# integrated_haptic.net
KiCad netlist of a schematic drawn in EAGLE
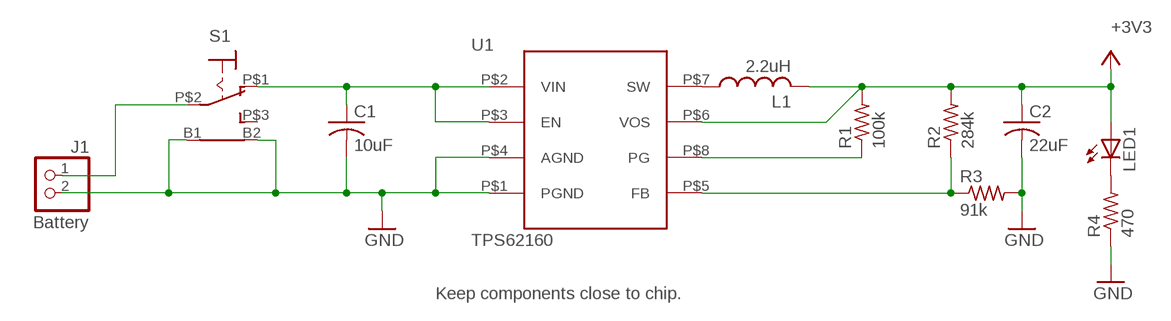
[diagram p0: schematic, sheet 1]
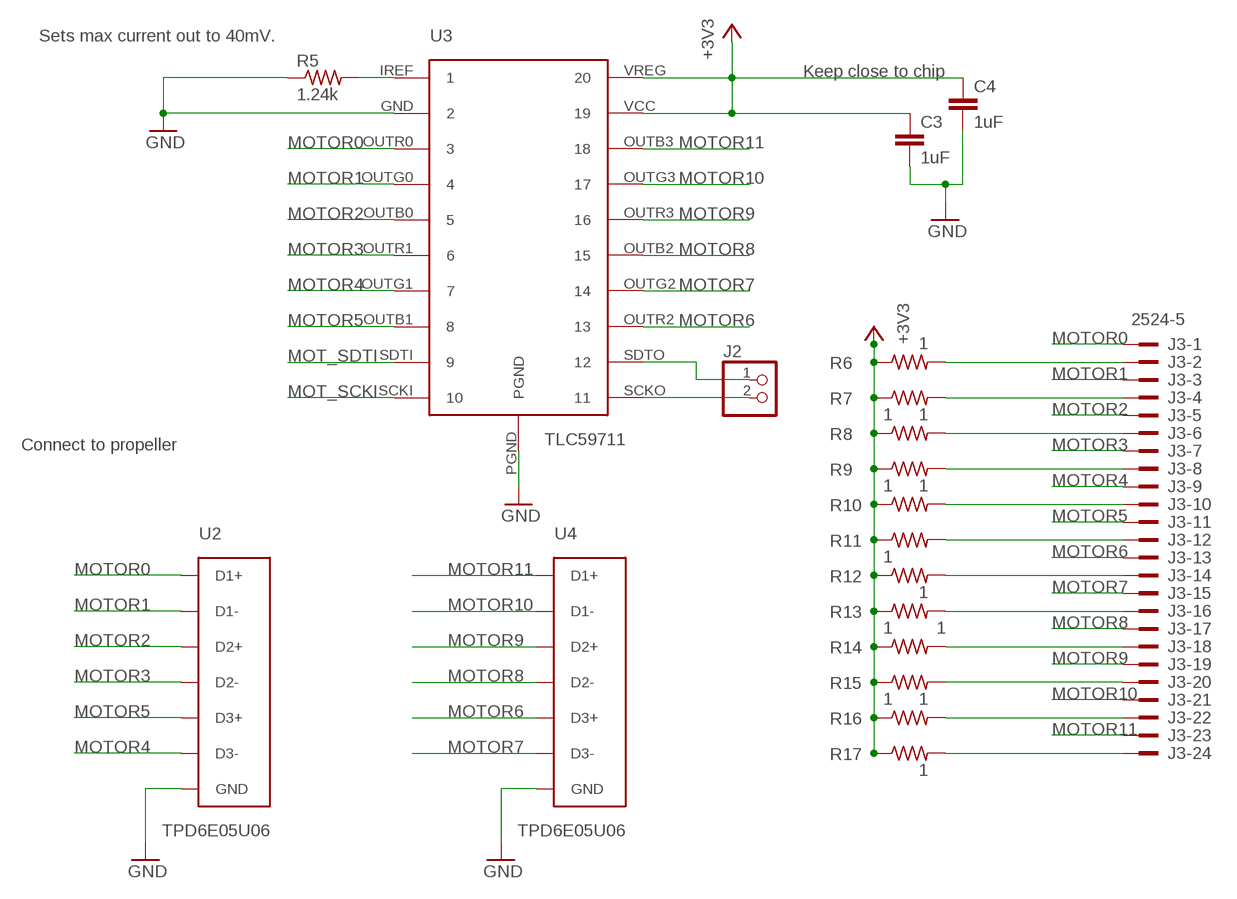
[diagram p1: schematic, sheet 2]
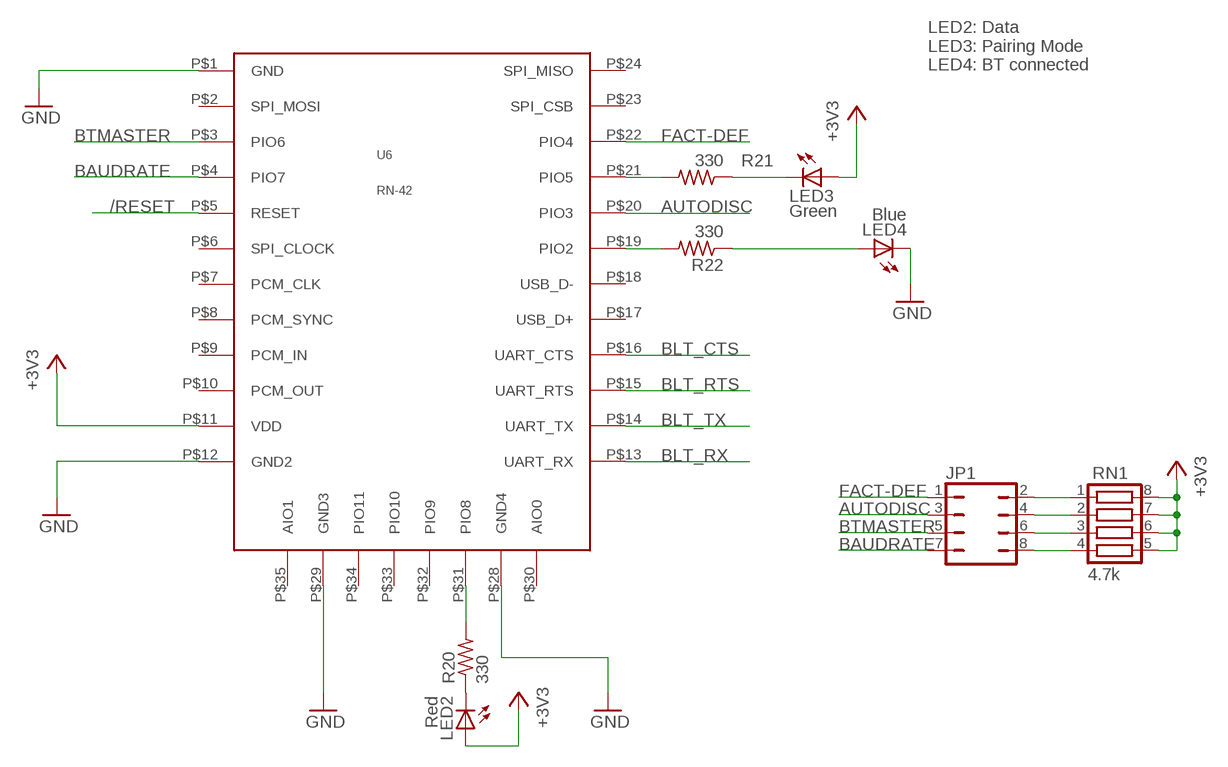
[diagram p2: schematic, sheet 3]
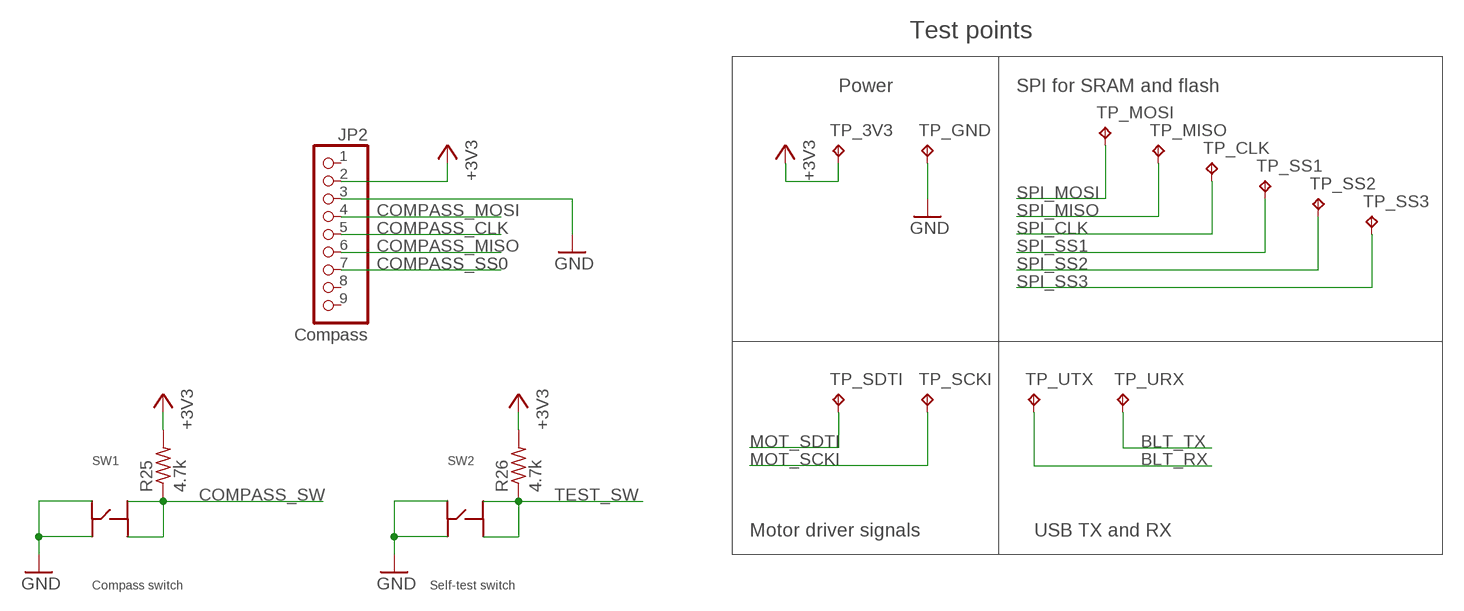
[diagram p3: schematic, sheet 4]
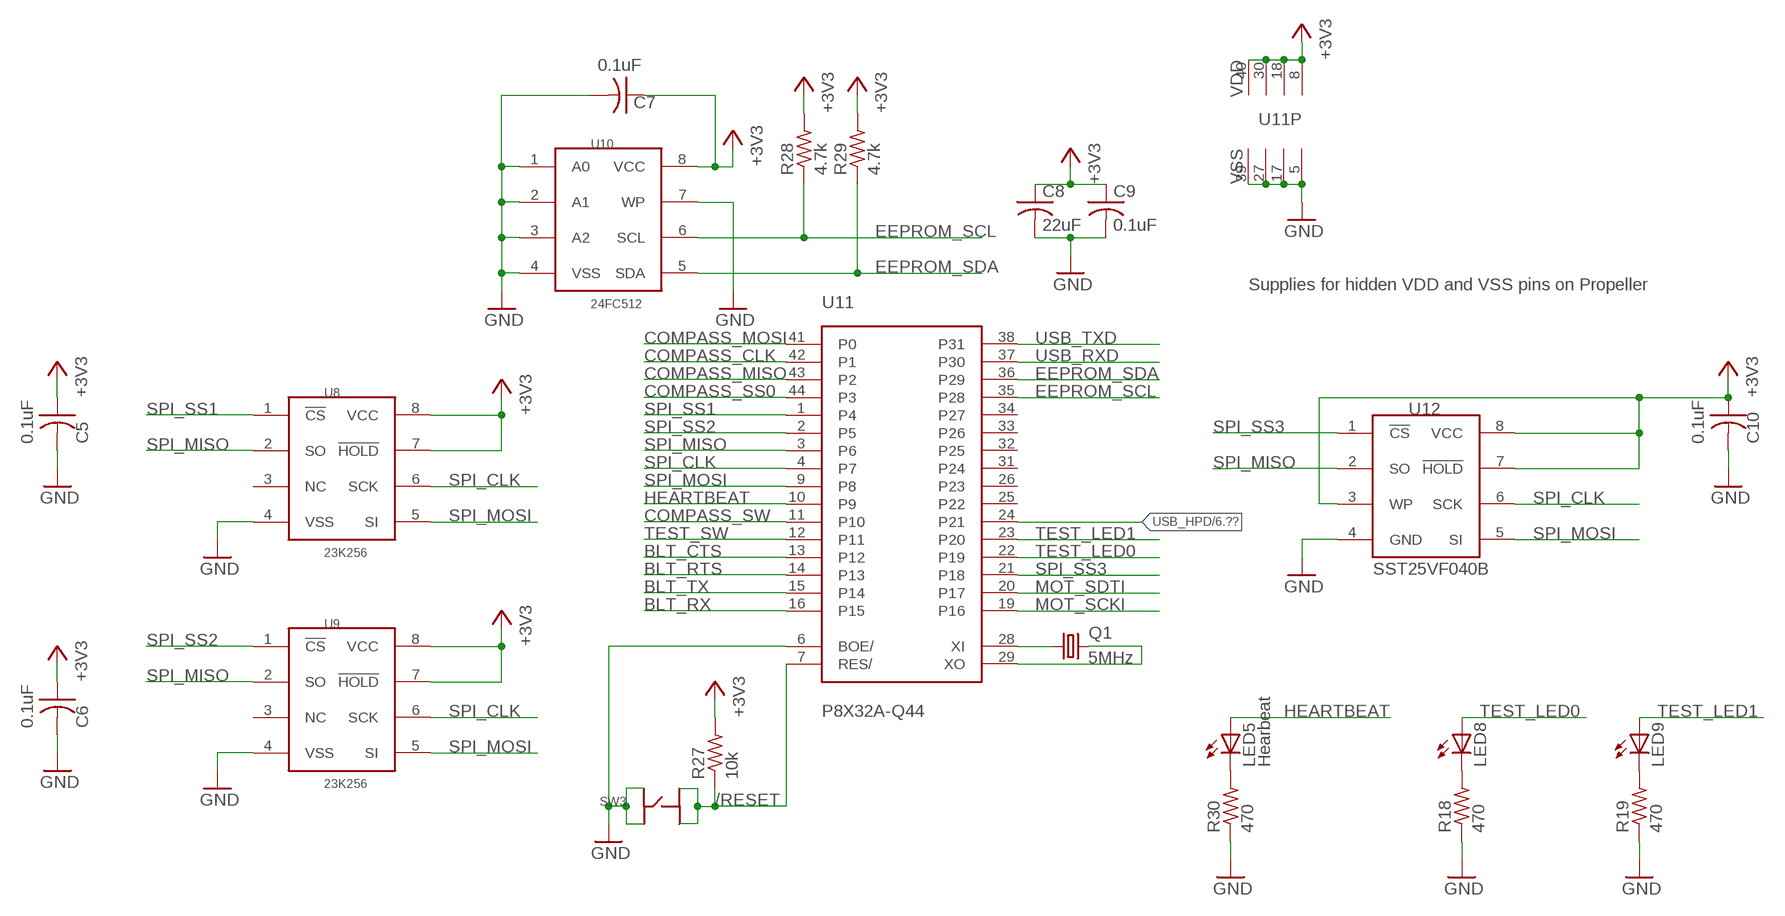
[diagram p4: schematic, sheet 5]
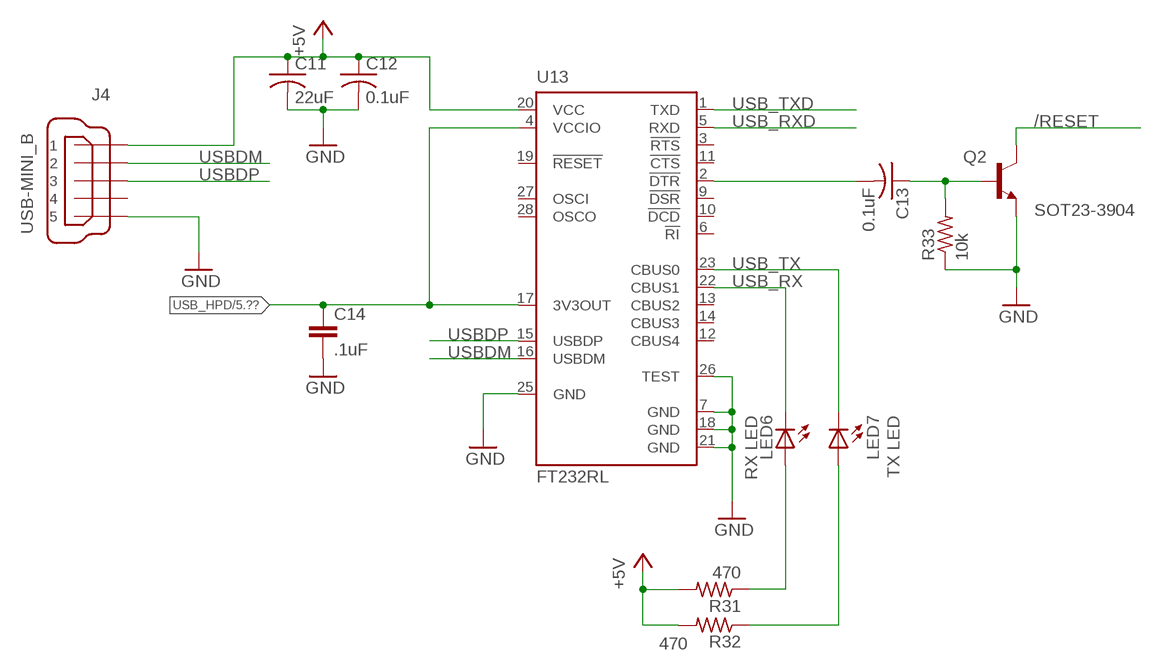
[diagram p5: schematic, sheet 6]

(export (version "E")
  (design (tool "Eeschema 10.0.6"))
  (components
    (comp (ref "C1")
      (value "10uF")
      (footprint "eagle-import:C1206K")
      (libsource (lib "eagle-import") (part "C-USC1206K"))
    )
    (comp (ref "C2")
      (value "22uF")
      (footprint "eagle-import:C1206K")
      (libsource (lib "eagle-import") (part "C-USC1206K"))
    )
    (comp (ref "J1")
      (value "Battery")
      (footprint "eagle-import:1X02")
      (libsource (lib "eagle-import") (part "PINHD-1X2"))
    )
    (comp (ref "L1")
      (value "2.2uH")
      (footprint "eagle-import:L2520P")
      (libsource (lib "eagle-import") (part "L-USL2520P"))
    )
    (comp (ref "LED1")
      (value "LEDCHIP-LED0805")
      (footprint "eagle-import:CHIP-LED0805")
      (libsource (lib "eagle-import") (part "LEDCHIP-LED0805"))
    )
    (comp (ref "R1")
      (value "100k")
      (footprint "eagle-import:R0603")
      (libsource (lib "eagle-import") (part "R-US_R0603"))
    )
    (comp (ref "R2")
      (value "284k")
      (footprint "eagle-import:R0603")
      (libsource (lib "eagle-import") (part "R-US_R0603"))
    )
    (comp (ref "R3")
      (value "91k")
      (footprint "eagle-import:R0603")
      (libsource (lib "eagle-import") (part "R-US_R0603"))
    )
    (comp (ref "R4")
      (value "470")
      (footprint "eagle-import:R0603")
      (libsource (lib "eagle-import") (part "R-US_R0603"))
    )
    (comp (ref "S1")
      (value "7101MD9AQE")
      (footprint "eagle-import:7101MD9A")
      (libsource (lib "eagle-import") (part "7101MD9AQE"))
    )
    (comp (ref "U1")
      (value "TPS62160")
      (footprint "eagle-import:VSSOP")
      (libsource (lib "eagle-import") (part "TPS62160"))
    )
    (comp (ref "JP2")
      (value "Compass")
      (footprint "eagle-import:1X09")
      (libsource (lib "eagle-import") (part "PINHD-1X9"))
    )
    (comp (ref "R25")
      (value "4.7k")
      (footprint "eagle-import:R0603")
      (libsource (lib "eagle-import") (part "R-US_R0603"))
    )
    (comp (ref "R26")
      (value "4.7k")
      (footprint "eagle-import:R0603")
      (libsource (lib "eagle-import") (part "R-US_R0603"))
    )
    (comp (ref "SW1")
      (value "Compass switch")
      (footprint "eagle-import:6MMX6MM")
      (libsource (lib "eagle-import") (part "PUSHBUTTON"))
    )
    (comp (ref "SW2")
      (value "Self-test switch")
      (footprint "eagle-import:6MMX6MM")
      (libsource (lib "eagle-import") (part "PUSHBUTTON"))
    )
    (comp (ref "TP_3V3")
      (value "TPPAD1-13")
      (footprint "eagle-import:P1-13")
      (libsource (lib "eagle-import") (part "TPPAD1-13"))
    )
    (comp (ref "TP_CLK")
      (value "TPPAD1-13")
      (footprint "eagle-import:P1-13")
      (libsource (lib "eagle-import") (part "TPPAD1-13"))
    )
    (comp (ref "TP_GND")
      (value "TPPAD1-13")
      (footprint "eagle-import:P1-13")
      (libsource (lib "eagle-import") (part "TPPAD1-13"))
    )
    (comp (ref "TP_MISO")
      (value "TPPAD1-13")
      (footprint "eagle-import:P1-13")
      (libsource (lib "eagle-import") (part "TPPAD1-13"))
    )
    (comp (ref "TP_MOSI")
      (value "SPI_MOSI")
      (footprint "eagle-import:P1-13")
      (libsource (lib "eagle-import") (part "TPPAD1-13"))
    )
    (comp (ref "TP_SCKI")
      (value "TPPAD1-13")
      (footprint "eagle-import:P1-13")
      (libsource (lib "eagle-import") (part "TPPAD1-13"))
    )
    (comp (ref "TP_SDTI")
      (value "TPPAD1-13")
      (footprint "eagle-import:P1-13")
      (libsource (lib "eagle-import") (part "TPPAD1-13"))
    )
    (comp (ref "TP_SS1")
      (value "TPPAD1-13")
      (footprint "eagle-import:P1-13")
      (libsource (lib "eagle-import") (part "TPPAD1-13"))
    )
    (comp (ref "TP_SS2")
      (value "TPPAD1-13")
      (footprint "eagle-import:P1-13")
      (libsource (lib "eagle-import") (part "TPPAD1-13"))
    )
    (comp (ref "TP_SS3")
      (value "TPPAD1-13")
      (footprint "eagle-import:P1-13")
      (libsource (lib "eagle-import") (part "TPPAD1-13"))
    )
    (comp (ref "TP_URX")
      (value "TPPAD1-13")
      (footprint "eagle-import:P1-13")
      (libsource (lib "eagle-import") (part "TPPAD1-13"))
    )
    (comp (ref "TP_UTX")
      (value "TPPAD1-13")
      (footprint "eagle-import:P1-13")
      (libsource (lib "eagle-import") (part "TPPAD1-13"))
    )
    (comp (ref "JP1")
      (value "JP4Q")
      (footprint "eagle-import:JP4Q")
      (libsource (lib "eagle-import") (part "JP4Q"))
    )
    (comp (ref "LED2")
      (value "Red")
      (footprint "eagle-import:CHIP-LED0805")
      (libsource (lib "eagle-import") (part "LEDCHIP-LED0805"))
    )
    (comp (ref "LED3")
      (value "Green")
      (footprint "eagle-import:CHIP-LED0805")
      (libsource (lib "eagle-import") (part "LEDCHIP-LED0805"))
    )
    (comp (ref "LED4")
      (value "Blue")
      (footprint "eagle-import:CHIP-LED0805")
      (libsource (lib "eagle-import") (part "LEDCHIP-LED0805"))
    )
    (comp (ref "R20")
      (value "330")
      (footprint "eagle-import:R0603")
      (libsource (lib "eagle-import") (part "R-US_R0603"))
    )
    (comp (ref "R21")
      (value "330")
      (footprint "eagle-import:R0603")
      (libsource (lib "eagle-import") (part "R-US_R0603"))
    )
    (comp (ref "R22")
      (value "330")
      (footprint "eagle-import:R0603")
      (libsource (lib "eagle-import") (part "R-US_R0603"))
    )
    (comp (ref "RN1")
      (value "4.7k")
      (footprint "eagle-import:CTS742C083")
      (libsource (lib "eagle-import") (part "CTS742C083"))
    )
    (comp (ref "U6")
      (value "RN-42")
      (footprint "eagle-import:RN-42")
      (libsource (lib "eagle-import") (part "RN-42"))
    )
    (comp (ref "C5")
      (value "0.1uF")
      (footprint "eagle-import:C0805K")
      (libsource (lib "eagle-import") (part "C-USC0805K"))
    )
    (comp (ref "C6")
      (value "0.1uF")
      (footprint "eagle-import:C0805K")
      (libsource (lib "eagle-import") (part "C-USC0805K"))
    )
    (comp (ref "C7")
      (value "0.1uF")
      (footprint "eagle-import:C0805K")
      (libsource (lib "eagle-import") (part "C-USC0805K"))
    )
    (comp (ref "C8")
      (value "22uF")
      (footprint "eagle-import:C1206K")
      (libsource (lib "eagle-import") (part "C-USC1206K"))
    )
    (comp (ref "C9")
      (value "0.1uF")
      (footprint "eagle-import:C0805K")
      (libsource (lib "eagle-import") (part "C-USC0805K"))
    )
    (comp (ref "C10")
      (value "0.1uF")
      (footprint "eagle-import:C0805K")
      (libsource (lib "eagle-import") (part "C-USC0805K"))
    )
    (comp (ref "LED5")
      (value "Hearbeat")
      (footprint "eagle-import:CHIP-LED0805")
      (libsource (lib "eagle-import") (part "LEDCHIP-LED0805"))
    )
    (comp (ref "LED8")
      (value "LEDCHIP-LED0805")
      (footprint "eagle-import:CHIP-LED0805")
      (libsource (lib "eagle-import") (part "LEDCHIP-LED0805"))
    )
    (comp (ref "LED9")
      (value "LEDCHIP-LED0805")
      (footprint "eagle-import:CHIP-LED0805")
      (libsource (lib "eagle-import") (part "LEDCHIP-LED0805"))
    )
    (comp (ref "Q1")
      (value "5MHz")
      (footprint "eagle-import:HC49UP")
      (libsource (lib "eagle-import") (part "CRYSTALHC49UP"))
    )
    (comp (ref "R18")
      (value "470")
      (footprint "eagle-import:R0603")
      (libsource (lib "eagle-import") (part "R-US_R0603"))
    )
    (comp (ref "R19")
      (value "470")
      (footprint "eagle-import:R0603")
      (libsource (lib "eagle-import") (part "R-US_R0603"))
    )
    (comp (ref "R27")
      (value "10k")
      (footprint "eagle-import:R0603")
      (libsource (lib "eagle-import") (part "R-US_R0603"))
    )
    (comp (ref "R28")
      (value "4.7k")
      (footprint "eagle-import:R0603")
      (libsource (lib "eagle-import") (part "R-US_R0603"))
    )
    (comp (ref "R29")
      (value "4.7k")
      (footprint "eagle-import:R0603")
      (libsource (lib "eagle-import") (part "R-US_R0603"))
    )
    (comp (ref "R30")
      (value "470")
      (footprint "eagle-import:R0603")
      (libsource (lib "eagle-import") (part "R-US_R0603"))
    )
    (comp (ref "SW3")
      (value "PUSHBUTTON")
      (footprint "eagle-import:6MMX6MM")
      (libsource (lib "eagle-import") (part "PUSHBUTTON"))
    )
    (comp (ref "U8")
      (value "23K256")
      (footprint "eagle-import:SOIC8")
      (libsource (lib "eagle-import") (part "23K256"))
    )
    (comp (ref "U9")
      (value "23K256")
      (footprint "eagle-import:SOIC8")
      (libsource (lib "eagle-import") (part "23K256"))
    )
    (comp (ref "U10")
      (value "24FC512")
      (footprint "eagle-import:SOIC8")
      (libsource (lib "eagle-import") (part "24FC512"))
    )
    (comp (ref "U11")
      (value "P8X32A-Q44")
      (footprint "eagle-import:P8X32A-Q44")
      (libsource (lib "eagle-import") (part "P8X32A-Q44"))
    )
    (comp (ref "U12")
      (value "SST25VF040B")
      (footprint "eagle-import:SOIC8")
      (libsource (lib "eagle-import") (part "SST25VF040B"))
    )
    (comp (ref "C3")
      (value "1uF")
      (footprint "eagle-import:C0805K")
      (libsource (lib "eagle-import") (part "resistor_C-EUC0805K"))
    )
    (comp (ref "C4")
      (value "1uF")
      (footprint "eagle-import:C0805K")
      (libsource (lib "eagle-import") (part "resistor_C-EUC0805K"))
    )
    (comp (ref "J2")
      (value "PINHD-1X2")
      (footprint "eagle-import:1X02")
      (libsource (lib "eagle-import") (part "PINHD-1X2"))
    )
    (comp (ref "J3")
      (value "2524-5")
      (footprint "eagle-import:PAK100_2500-5-24")
      (libsource (lib "eagle-import") (part "2524-5"))
    )
    (comp (ref "R5")
      (value "1.24k")
      (footprint "eagle-import:R0603")
      (libsource (lib "eagle-import") (part "R-US_R0603"))
    )
    (comp (ref "R6")
      (value "1")
      (footprint "eagle-import:R0805")
      (libsource (lib "eagle-import") (part "resistor_R-US_R0805"))
    )
    (comp (ref "R7")
      (value "1")
      (footprint "eagle-import:R0805")
      (libsource (lib "eagle-import") (part "resistor_R-US_R0805"))
    )
    (comp (ref "R8")
      (value "1")
      (footprint "eagle-import:R0805")
      (libsource (lib "eagle-import") (part "resistor_R-US_R0805"))
    )
    (comp (ref "R9")
      (value "1")
      (footprint "eagle-import:R0805")
      (libsource (lib "eagle-import") (part "resistor_R-US_R0805"))
    )
    (comp (ref "R10")
      (value "1")
      (footprint "eagle-import:R0805")
      (libsource (lib "eagle-import") (part "resistor_R-US_R0805"))
    )
    (comp (ref "R11")
      (value "1")
      (footprint "eagle-import:R0805")
      (libsource (lib "eagle-import") (part "resistor_R-US_R0805"))
    )
    (comp (ref "R12")
      (value "1")
      (footprint "eagle-import:R0805")
      (libsource (lib "eagle-import") (part "resistor_R-US_R0805"))
    )
    (comp (ref "R13")
      (value "1")
      (footprint "eagle-import:R0805")
      (libsource (lib "eagle-import") (part "resistor_R-US_R0805"))
    )
    (comp (ref "R14")
      (value "1")
      (footprint "eagle-import:R0805")
      (libsource (lib "eagle-import") (part "resistor_R-US_R0805"))
    )
    (comp (ref "R15")
      (value "1")
      (footprint "eagle-import:R0805")
      (libsource (lib "eagle-import") (part "resistor_R-US_R0805"))
    )
    (comp (ref "R16")
      (value "1")
      (footprint "eagle-import:R0805")
      (libsource (lib "eagle-import") (part "resistor_R-US_R0805"))
    )
    (comp (ref "R17")
      (value "1")
      (footprint "eagle-import:R0805")
      (libsource (lib "eagle-import") (part "resistor_R-US_R0805"))
    )
    (comp (ref "U2")
      (value "TPD6E05U06")
      (footprint "eagle-import:PUQFN-N14")
      (libsource (lib "eagle-import") (part "TPD6E05U06"))
    )
    (comp (ref "U3")
      (value "TLC59711")
      (footprint "eagle-import:TLC59711")
      (libsource (lib "eagle-import") (part "TLC59711"))
    )
    (comp (ref "U4")
      (value "TPD6E05U06")
      (footprint "eagle-import:PUQFN-N14")
      (libsource (lib "eagle-import") (part "TPD6E05U06"))
    )
    (comp (ref "C11")
      (value "22uF")
      (footprint "eagle-import:C1206K")
      (libsource (lib "eagle-import") (part "C-USC1206K"))
    )
    (comp (ref "C12")
      (value "0.1uF")
      (footprint "eagle-import:C0805K")
      (libsource (lib "eagle-import") (part "C-USC0805K"))
    )
    (comp (ref "C13")
      (value "0.1uF")
      (footprint "eagle-import:C0805K")
      (libsource (lib "eagle-import") (part "C-USC0805K"))
    )
    (comp (ref "C14")
      (value ".1uF")
      (footprint "eagle-import:C0805")
      (libsource (lib "eagle-import") (part "C-EUC0805"))
    )
    (comp (ref "J4")
      (value "USB-MINI_B")
      (footprint "eagle-import:USB_MINI_B")
      (libsource (lib "eagle-import") (part "USB-MINI_B"))
    )
    (comp (ref "LED6")
      (value "RX LED")
      (footprint "eagle-import:CHIP-LED0805")
      (libsource (lib "eagle-import") (part "LEDCHIP-LED0805"))
    )
    (comp (ref "LED7")
      (value "TX LED")
      (footprint "eagle-import:CHIP-LED0805")
      (libsource (lib "eagle-import") (part "LEDCHIP-LED0805"))
    )
    (comp (ref "Q2")
      (value "SOT23-3904")
      (footprint "eagle-import:SOT23-BEC")
      (libsource (lib "eagle-import") (part "-NPN-SOT23-BECMMBT918LT1"))
    )
    (comp (ref "R31")
      (value "470")
      (footprint "eagle-import:R0603")
      (libsource (lib "eagle-import") (part "R-US_R0603"))
    )
    (comp (ref "R32")
      (value "470")
      (footprint "eagle-import:R0603")
      (libsource (lib "eagle-import") (part "R-US_R0603"))
    )
    (comp (ref "R33")
      (value "10k")
      (footprint "eagle-import:R0603")
      (libsource (lib "eagle-import") (part "R-US_R0603"))
    )
    (comp (ref "U13")
      (value "FT232RL")
      (footprint "eagle-import:SSOP28")
      (libsource (lib "eagle-import") (part "FT232RL"))
    )
  )
  (nets
    (net (code "1") (name "+3V3") (class "Default")
      (node (ref "C10") (pin "1") (pinfunction "1_1") (pintype "passive"))
      (node (ref "C2") (pin "1") (pinfunction "1_1") (pintype "passive"))
      (node (ref "C3") (pin "1") (pinfunction "1_1") (pintype "passive"))
      (node (ref "C4") (pin "1") (pinfunction "1_1") (pintype "passive"))
      (node (ref "C5") (pin "1") (pinfunction "1_1") (pintype "passive"))
      (node (ref "C6") (pin "1") (pinfunction "1_1") (pintype "passive"))
      (node (ref "C7") (pin "1") (pinfunction "1_1") (pintype "passive"))
      (node (ref "C8") (pin "1") (pinfunction "1_1") (pintype "passive"))
      (node (ref "C9") (pin "1") (pinfunction "1_1") (pintype "passive"))
      (node (ref "JP2") (pin "2") (pinfunction "2_2") (pintype "passive"))
      (node (ref "L1") (pin "2") (pinfunction "2_2") (pintype "passive"))
      (node (ref "LED1") (pin "A") (pinfunction "A_A") (pintype "passive"))
      (node (ref "LED2") (pin "A") (pinfunction "A_A") (pintype "passive"))
      (node (ref "LED3") (pin "A") (pinfunction "A_A") (pintype "passive"))
      (node (ref "R1") (pin "2") (pinfunction "2_2") (pintype "passive"))
      (node (ref "R10") (pin "1") (pinfunction "1_1") (pintype "passive"))
      (node (ref "R11") (pin "1") (pinfunction "1_1") (pintype "passive"))
      (node (ref "R12") (pin "1") (pinfunction "1_1") (pintype "passive"))
      (node (ref "R13") (pin "1") (pinfunction "1_1") (pintype "passive"))
      (node (ref "R14") (pin "1") (pinfunction "1_1") (pintype "passive"))
      (node (ref "R15") (pin "1") (pinfunction "1_1") (pintype "passive"))
      (node (ref "R16") (pin "1") (pinfunction "1_1") (pintype "passive"))
      (node (ref "R17") (pin "1") (pinfunction "1_1") (pintype "passive"))
      (node (ref "R2") (pin "2") (pinfunction "2_2") (pintype "passive"))
      (node (ref "R25") (pin "2") (pinfunction "2_2") (pintype "passive"))
      (node (ref "R26") (pin "2") (pinfunction "2_2") (pintype "passive"))
      (node (ref "R27") (pin "2") (pinfunction "2_2") (pintype "passive"))
      (node (ref "R28") (pin "2") (pinfunction "2_2") (pintype "passive"))
      (node (ref "R29") (pin "2") (pinfunction "2_2") (pintype "passive"))
      (node (ref "R6") (pin "1") (pinfunction "1_1") (pintype "passive"))
      (node (ref "R7") (pin "1") (pinfunction "1_1") (pintype "passive"))
      (node (ref "R8") (pin "1") (pinfunction "1_1") (pintype "passive"))
      (node (ref "R9") (pin "1") (pinfunction "1_1") (pintype "passive"))
      (node (ref "RN1") (pin "5") (pinfunction "5_5") (pintype "passive"))
      (node (ref "RN1") (pin "6") (pinfunction "6_6") (pintype "passive"))
      (node (ref "RN1") (pin "7") (pinfunction "7_7") (pintype "passive"))
      (node (ref "RN1") (pin "8") (pinfunction "8_8") (pintype "passive"))
      (node (ref "TP_3V3") (pin "TP") (pinfunction "TP_TP") (pintype "input"))
      (node (ref "U1") (pin "P$6") (pinfunction "VOS_P$6") (pintype "bidirectional"))
      (node (ref "U10") (pin "8") (pinfunction "VCC_8") (pintype "bidirectional"))
      (node (ref "U11") (pin "18") (pinfunction "VDD_18") (pintype "power_in"))
      (node (ref "U11") (pin "30") (pinfunction "VDD_30") (pintype "power_in"))
      (node (ref "U11") (pin "40") (pinfunction "VDD_40") (pintype "power_in"))
      (node (ref "U11") (pin "8") (pinfunction "VDD_8") (pintype "power_in"))
      (node (ref "U12") (pin "3") (pinfunction "WP_3") (pintype "bidirectional"))
      (node (ref "U12") (pin "7") (pinfunction "~{HOLD}_7") (pintype "bidirectional"))
      (node (ref "U12") (pin "8") (pinfunction "VCC_8") (pintype "bidirectional"))
      (node (ref "U3") (pin "VCC") (pinfunction "19_VCC") (pintype "bidirectional"))
      (node (ref "U3") (pin "VREG") (pinfunction "20_VREG") (pintype "bidirectional"))
      (node (ref "U6") (pin "P$11") (pinfunction "VDD_P$11") (pintype "bidirectional"))
      (node (ref "U8") (pin "7") (pinfunction "~{HOLD}_7") (pintype "bidirectional"))
      (node (ref "U8") (pin "8") (pinfunction "VCC_8") (pintype "bidirectional"))
      (node (ref "U9") (pin "7") (pinfunction "~{HOLD}_7") (pintype "bidirectional"))
      (node (ref "U9") (pin "8") (pinfunction "VCC_8") (pintype "bidirectional"))
    )
    (net (code "2") (name "+5V") (class "Default")
      (node (ref "C11") (pin "1") (pinfunction "1_1") (pintype "passive"))
      (node (ref "C12") (pin "1") (pinfunction "1_1") (pintype "passive"))
      (node (ref "J4") (pin "1") (pinfunction "1_1") (pintype "passive"))
      (node (ref "R31") (pin "2") (pinfunction "2_2") (pintype "passive"))
      (node (ref "R32") (pin "2") (pinfunction "2_2") (pintype "passive"))
      (node (ref "U13") (pin "20") (pinfunction "VCC_20") (pintype "power_in"))
    )
    (net (code "3") (name "AUTODISC") (class "Default")
      (node (ref "JP1") (pin "3") (pinfunction "3_3") (pintype "passive"))
      (node (ref "U6") (pin "P$20") (pinfunction "PIO3_P$20") (pintype "bidirectional"))
    )
    (net (code "4") (name "BAUDRATE") (class "Default")
      (node (ref "JP1") (pin "7") (pinfunction "7_7") (pintype "passive"))
      (node (ref "U6") (pin "P$4") (pinfunction "PIO7_P$4") (pintype "bidirectional"))
    )
    (net (code "5") (name "BLT_CTS") (class "Default")
      (node (ref "U11") (pin "13") (pinfunction "P12_13") (pintype "bidirectional"))
      (node (ref "U6") (pin "P$16") (pinfunction "UART_CTS_P$16") (pintype "bidirectional"))
    )
    (net (code "6") (name "BLT_RTS") (class "Default")
      (node (ref "U11") (pin "14") (pinfunction "P13_14") (pintype "bidirectional"))
      (node (ref "U6") (pin "P$15") (pinfunction "UART_RTS_P$15") (pintype "bidirectional"))
    )
    (net (code "7") (name "BLT_RX") (class "Default")
      (node (ref "TP_UTX") (pin "TP") (pinfunction "TP_TP") (pintype "input"))
      (node (ref "U11") (pin "16") (pinfunction "P15_16") (pintype "bidirectional"))
      (node (ref "U6") (pin "P$13") (pinfunction "UART_RX_P$13") (pintype "bidirectional"))
    )
    (net (code "8") (name "BLT_TX") (class "Default")
      (node (ref "TP_URX") (pin "TP") (pinfunction "TP_TP") (pintype "input"))
      (node (ref "U11") (pin "15") (pinfunction "P14_15") (pintype "bidirectional"))
      (node (ref "U6") (pin "P$14") (pinfunction "UART_TX_P$14") (pintype "bidirectional"))
    )
    (net (code "9") (name "BTMASTER") (class "Default")
      (node (ref "JP1") (pin "5") (pinfunction "5_5") (pintype "passive"))
      (node (ref "U6") (pin "P$3") (pinfunction "PIO6_P$3") (pintype "bidirectional"))
    )
    (net (code "10") (name "COMPASS_CLK") (class "Default")
      (node (ref "JP2") (pin "5") (pinfunction "5_5") (pintype "passive"))
      (node (ref "U11") (pin "42") (pinfunction "P1_42") (pintype "bidirectional"))
    )
    (net (code "11") (name "COMPASS_MISO") (class "Default")
      (node (ref "JP2") (pin "6") (pinfunction "6_6") (pintype "passive"))
      (node (ref "U11") (pin "43") (pinfunction "P2_43") (pintype "bidirectional"))
    )
    (net (code "12") (name "COMPASS_MOSI") (class "Default")
      (node (ref "JP2") (pin "4") (pinfunction "4_4") (pintype "passive"))
      (node (ref "U11") (pin "41") (pinfunction "P0_41") (pintype "bidirectional"))
    )
    (net (code "13") (name "COMPASS_SS0") (class "Default")
      (node (ref "JP2") (pin "7") (pinfunction "7_7") (pintype "passive"))
      (node (ref "U11") (pin "44") (pinfunction "P3_44") (pintype "bidirectional"))
    )
    (net (code "14") (name "COMPASS_SW") (class "Default")
      (node (ref "R25") (pin "1") (pinfunction "1_1") (pintype "passive"))
      (node (ref "SW1") (pin "P$2") (pinfunction "P$3_P$2") (pintype "bidirectional"))
      (node (ref "SW1") (pin "P$4") (pinfunction "P$4_P$4") (pintype "bidirectional"))
      (node (ref "U11") (pin "11") (pinfunction "P10_11") (pintype "bidirectional"))
    )
    (net (code "15") (name "EEPROM_SCL") (class "Default")
      (node (ref "R28") (pin "1") (pinfunction "1_1") (pintype "passive"))
      (node (ref "U10") (pin "6") (pinfunction "SCL_6") (pintype "bidirectional"))
      (node (ref "U11") (pin "35") (pinfunction "P28_35") (pintype "bidirectional"))
    )
    (net (code "16") (name "EEPROM_SDA") (class "Default")
      (node (ref "R29") (pin "1") (pinfunction "1_1") (pintype "passive"))
      (node (ref "U10") (pin "5") (pinfunction "SDA_5") (pintype "bidirectional"))
      (node (ref "U11") (pin "36") (pinfunction "P29_36") (pintype "bidirectional"))
    )
    (net (code "17") (name "FACT-DEF") (class "Default")
      (node (ref "JP1") (pin "1") (pinfunction "1_1") (pintype "passive"))
      (node (ref "U6") (pin "P$22") (pinfunction "PIO4_P$22") (pintype "bidirectional"))
    )
    (net (code "18") (name "GND") (class "Default")
      (node (ref "C1") (pin "2") (pinfunction "2_2") (pintype "passive"))
      (node (ref "C10") (pin "2") (pinfunction "2_2") (pintype "passive"))
      (node (ref "C11") (pin "2") (pinfunction "2_2") (pintype "passive"))
      (node (ref "C12") (pin "2") (pinfunction "2_2") (pintype "passive"))
      (node (ref "C14") (pin "2") (pinfunction "2_2") (pintype "passive"))
      (node (ref "C2") (pin "2") (pinfunction "2_2") (pintype "passive"))
      (node (ref "C3") (pin "2") (pinfunction "2_2") (pintype "passive"))
      (node (ref "C4") (pin "2") (pinfunction "2_2") (pintype "passive"))
      (node (ref "C5") (pin "2") (pinfunction "2_2") (pintype "passive"))
      (node (ref "C6") (pin "2") (pinfunction "2_2") (pintype "passive"))
      (node (ref "C7") (pin "2") (pinfunction "2_2") (pintype "passive"))
      (node (ref "C8") (pin "2") (pinfunction "2_2") (pintype "passive"))
      (node (ref "C9") (pin "2") (pinfunction "2_2") (pintype "passive"))
      (node (ref "J1") (pin "2") (pinfunction "2_2") (pintype "passive"))
      (node (ref "J4") (pin "5") (pinfunction "5_5") (pintype "passive"))
      (node (ref "JP2") (pin "3") (pinfunction "3_3") (pintype "passive"))
      (node (ref "LED4") (pin "C") (pinfunction "C_C") (pintype "passive"))
      (node (ref "Q2") (pin "E") (pinfunction "E_E") (pintype "passive"))
      (node (ref "R18") (pin "1") (pinfunction "1_1") (pintype "passive"))
      (node (ref "R19") (pin "1") (pinfunction "1_1") (pintype "passive"))
      (node (ref "R3") (pin "2") (pinfunction "2_2") (pintype "passive"))
      (node (ref "R30") (pin "1") (pinfunction "1_1") (pintype "passive"))
      (node (ref "R33") (pin "1") (pinfunction "1_1") (pintype "passive"))
      (node (ref "R4") (pin "1") (pinfunction "1_1") (pintype "passive"))
      (node (ref "R5") (pin "1") (pinfunction "1_1") (pintype "passive"))
      (node (ref "S1") (pin "B1") (pinfunction "B_B1") (pintype "passive"))
      (node (ref "S1") (pin "B2") (pinfunction "B1_B2") (pintype "passive"))
      (node (ref "SW1") (pin "P$1") (pinfunction "P$1_P$1") (pintype "bidirectional"))
      (node (ref "SW1") (pin "P$3") (pinfunction "P$2_P$3") (pintype "bidirectional"))
      (node (ref "SW2") (pin "P$1") (pinfunction "P$1_P$1") (pintype "bidirectional"))
      (node (ref "SW2") (pin "P$3") (pinfunction "P$2_P$3") (pintype "bidirectional"))
      (node (ref "SW3") (pin "P$1") (pinfunction "P$1_P$1") (pintype "bidirectional"))
      (node (ref "SW3") (pin "P$3") (pinfunction "P$2_P$3") (pintype "bidirectional"))
      (node (ref "TP_GND") (pin "TP") (pinfunction "TP_TP") (pintype "input"))
      (node (ref "U1") (pin "P$1") (pinfunction "PGND_P$1") (pintype "bidirectional"))
      (node (ref "U1") (pin "P$4") (pinfunction "AGND_P$4") (pintype "bidirectional"))
      (node (ref "U10") (pin "1") (pinfunction "A0_1") (pintype "bidirectional"))
      (node (ref "U10") (pin "2") (pinfunction "A1_2") (pintype "bidirectional"))
      (node (ref "U10") (pin "3") (pinfunction "A2_3") (pintype "bidirectional"))
      (node (ref "U10") (pin "4") (pinfunction "VSS_4") (pintype "bidirectional"))
      (node (ref "U10") (pin "7") (pinfunction "WP_7") (pintype "bidirectional"))
      (node (ref "U11") (pin "17") (pinfunction "VSS_17") (pintype "power_in"))
      (node (ref "U11") (pin "27") (pinfunction "VSS_27") (pintype "power_in"))
      (node (ref "U11") (pin "39") (pinfunction "VSS_39") (pintype "power_in"))
      (node (ref "U11") (pin "5") (pinfunction "VSS_5") (pintype "power_in"))
      (node (ref "U11") (pin "6") (pinfunction "BOE/_6") (pintype "input"))
      (node (ref "U12") (pin "4") (pinfunction "GND_4") (pintype "bidirectional"))
      (node (ref "U13") (pin "18") (pinfunction "GND_18") (pintype "power_in"))
      (node (ref "U13") (pin "21") (pinfunction "GND_21") (pintype "power_in"))
      (node (ref "U13") (pin "25") (pinfunction "GND_25") (pintype "power_in"))
      (node (ref "U13") (pin "26") (pinfunction "TEST_26") (pintype "input"))
      (node (ref "U13") (pin "7") (pinfunction "GND_7") (pintype "power_in"))
      (node (ref "U2") (pin "P$10") (pinfunction "GND_P$10") (pintype "power_in"))
      (node (ref "U2") (pin "P$5") (pinfunction "GND_P$5") (pintype "power_in"))
      (node (ref "U3") (pin "GND") (pinfunction "2_GND") (pintype "bidirectional"))
      (node (ref "U3") (pin "PGND") (pinfunction "PGND_PGND") (pintype "bidirectional"))
      (node (ref "U4") (pin "P$10") (pinfunction "GND_P$10") (pintype "power_in"))
      (node (ref "U4") (pin "P$5") (pinfunction "GND_P$5") (pintype "power_in"))
      (node (ref "U6") (pin "P$1") (pinfunction "GND_P$1") (pintype "bidirectional"))
      (node (ref "U6") (pin "P$12") (pinfunction "GND2_P$12") (pintype "bidirectional"))
      (node (ref "U6") (pin "P$28") (pinfunction "GND4_P$28") (pintype "bidirectional"))
      (node (ref "U6") (pin "P$29") (pinfunction "GND3_P$29") (pintype "bidirectional"))
      (node (ref "U8") (pin "4") (pinfunction "VSS_4") (pintype "bidirectional"))
      (node (ref "U9") (pin "4") (pinfunction "VSS_4") (pintype "bidirectional"))
    )
    (net (code "19") (name "HEARTBEAT") (class "Default")
      (node (ref "LED5") (pin "A") (pinfunction "A_A") (pintype "passive"))
      (node (ref "U11") (pin "10") (pinfunction "P9_10") (pintype "bidirectional"))
    )
    (net (code "20") (name "MOTOR0") (class "Default")
      (node (ref "J3") (pin "1") (pinfunction "KL_1") (pintype "passive"))
      (node (ref "U2") (pin "P$1") (pinfunction "D1+_P$1") (pintype "bidirectional"))
      (node (ref "U2") (pin "P$14") (pinfunction "D1+_P$14") (pintype "bidirectional"))
      (node (ref "U3") (pin "OUTR0") (pinfunction "3_OUTR0") (pintype "bidirectional"))
    )
    (net (code "21") (name "MOTOR1") (class "Default")
      (node (ref "J3") (pin "3") (pinfunction "KL_3") (pintype "passive"))
      (node (ref "U2") (pin "P$13") (pinfunction "D1-_P$13") (pintype "bidirectional"))
      (node (ref "U2") (pin "P$2") (pinfunction "D1-_P$2") (pintype "bidirectional"))
      (node (ref "U3") (pin "OUTG0") (pinfunction "4_OUTG0") (pintype "bidirectional"))
    )
    (net (code "22") (name "MOTOR2") (class "Default")
      (node (ref "J3") (pin "5") (pinfunction "KL_5") (pintype "passive"))
      (node (ref "U2") (pin "P$12") (pinfunction "D2+_P$12") (pintype "bidirectional"))
      (node (ref "U2") (pin "P$3") (pinfunction "D2+_P$3") (pintype "bidirectional"))
      (node (ref "U3") (pin "OUTB0") (pinfunction "5_OUTB0") (pintype "bidirectional"))
    )
    (net (code "23") (name "MOTOR3") (class "Default")
      (node (ref "J3") (pin "7") (pinfunction "KL_7") (pintype "passive"))
      (node (ref "U2") (pin "P$11") (pinfunction "D2-_P$11") (pintype "bidirectional"))
      (node (ref "U2") (pin "P$4") (pinfunction "D2-_P$4") (pintype "bidirectional"))
      (node (ref "U3") (pin "OUTR1") (pinfunction "6_OUTR1") (pintype "bidirectional"))
    )
    (net (code "24") (name "MOTOR4") (class "Default")
      (node (ref "J3") (pin "9") (pinfunction "KL_9") (pintype "passive"))
      (node (ref "U2") (pin "P$6") (pinfunction "D3-_P$6") (pintype "bidirectional"))
      (node (ref "U2") (pin "P$9") (pinfunction "D3-_P$9") (pintype "bidirectional"))
      (node (ref "U3") (pin "OUTG1") (pinfunction "7_OUTG1") (pintype "bidirectional"))
    )
    (net (code "25") (name "MOTOR5") (class "Default")
      (node (ref "J3") (pin "11") (pinfunction "KL_11") (pintype "passive"))
      (node (ref "U2") (pin "P$7") (pinfunction "D3+_P$7") (pintype "bidirectional"))
      (node (ref "U2") (pin "P$8") (pinfunction "D3+_P$8") (pintype "bidirectional"))
      (node (ref "U3") (pin "OUTB1") (pinfunction "8_OUTB1") (pintype "bidirectional"))
    )
    (net (code "26") (name "MOTOR6") (class "Default")
      (node (ref "J3") (pin "13") (pinfunction "KL_13") (pintype "passive"))
      (node (ref "U3") (pin "OUTR2") (pinfunction "13_OUTR2") (pintype "bidirectional"))
      (node (ref "U4") (pin "P$7") (pinfunction "D3+_P$7") (pintype "bidirectional"))
      (node (ref "U4") (pin "P$8") (pinfunction "D3+_P$8") (pintype "bidirectional"))
    )
    (net (code "27") (name "MOTOR7") (class "Default")
      (node (ref "J3") (pin "15") (pinfunction "KL_15") (pintype "passive"))
      (node (ref "U3") (pin "OUTG2") (pinfunction "14_OUTG2") (pintype "bidirectional"))
      (node (ref "U4") (pin "P$6") (pinfunction "D3-_P$6") (pintype "bidirectional"))
      (node (ref "U4") (pin "P$9") (pinfunction "D3-_P$9") (pintype "bidirectional"))
    )
    (net (code "28") (name "MOTOR8") (class "Default")
      (node (ref "J3") (pin "17") (pinfunction "KL_17") (pintype "passive"))
      (node (ref "U3") (pin "OUTB2") (pinfunction "15_OUTB2") (pintype "bidirectional"))
      (node (ref "U4") (pin "P$11") (pinfunction "D2-_P$11") (pintype "bidirectional"))
      (node (ref "U4") (pin "P$4") (pinfunction "D2-_P$4") (pintype "bidirectional"))
    )
    (net (code "29") (name "MOTOR9") (class "Default")
      (node (ref "J3") (pin "19") (pinfunction "KL_19") (pintype "passive"))
      (node (ref "U3") (pin "OUTR3") (pinfunction "16_OUTR3") (pintype "bidirectional"))
      (node (ref "U4") (pin "P$12") (pinfunction "D2+_P$12") (pintype "bidirectional"))
      (node (ref "U4") (pin "P$3") (pinfunction "D2+_P$3") (pintype "bidirectional"))
    )
    (net (code "30") (name "MOTOR10") (class "Default")
      (node (ref "J3") (pin "21") (pinfunction "KL_21") (pintype "passive"))
      (node (ref "U3") (pin "OUTG3") (pinfunction "17_OUTG3") (pintype "bidirectional"))
      (node (ref "U4") (pin "P$13") (pinfunction "D1-_P$13") (pintype "bidirectional"))
      (node (ref "U4") (pin "P$2") (pinfunction "D1-_P$2") (pintype "bidirectional"))
    )
    (net (code "31") (name "MOTOR11") (class "Default")
      (node (ref "J3") (pin "23") (pinfunction "KL_23") (pintype "passive"))
      (node (ref "U3") (pin "OUTB3") (pinfunction "18_OUTB3") (pintype "bidirectional"))
      (node (ref "U4") (pin "P$1") (pinfunction "D1+_P$1") (pintype "bidirectional"))
      (node (ref "U4") (pin "P$14") (pinfunction "D1+_P$14") (pintype "bidirectional"))
    )
    (net (code "32") (name "MOT_SCKI") (class "Default")
      (node (ref "TP_SCKI") (pin "TP") (pinfunction "TP_TP") (pintype "input"))
      (node (ref "U11") (pin "19") (pinfunction "P16_19") (pintype "bidirectional"))
      (node (ref "U3") (pin "SCKI") (pinfunction "10_SCKI") (pintype "bidirectional"))
    )
    (net (code "33") (name "MOT_SDTI") (class "Default")
      (node (ref "TP_SDTI") (pin "TP") (pinfunction "TP_TP") (pintype "input"))
      (node (ref "U11") (pin "20") (pinfunction "P17_20") (pintype "bidirectional"))
      (node (ref "U3") (pin "SDTI") (pinfunction "9_SDTI") (pintype "bidirectional"))
    )
    (net (code "34") (name "Net-(C13-Pad1)") (class "Default")
      (node (ref "C13") (pin "1") (pinfunction "1_1") (pintype "passive"))
      (node (ref "Q2") (pin "B") (pinfunction "B_B") (pintype "passive"))
      (node (ref "R33") (pin "2") (pinfunction "2_2") (pintype "passive"))
    )
    (net (code "35") (name "Net-(J3B-KL)") (class "Default")
      (node (ref "J3") (pin "10") (pinfunction "KL_10") (pintype "passive"))
      (node (ref "R10") (pin "2") (pinfunction "2_2") (pintype "passive"))
    )
    (net (code "36") (name "Net-(J3D-KL)") (class "Default")
      (node (ref "J3") (pin "12") (pinfunction "KL_12") (pintype "passive"))
      (node (ref "R11") (pin "2") (pinfunction "2_2") (pintype "passive"))
    )
    (net (code "37") (name "Net-(J3F-KL)") (class "Default")
      (node (ref "J3") (pin "14") (pinfunction "KL_14") (pintype "passive"))
      (node (ref "R12") (pin "2") (pinfunction "2_2") (pintype "passive"))
    )
    (net (code "38") (name "Net-(J3H-KL)") (class "Default")
      (node (ref "J3") (pin "16") (pinfunction "KL_16") (pintype "passive"))
      (node (ref "R13") (pin "2") (pinfunction "2_2") (pintype "passive"))
    )
    (net (code "39") (name "Net-(J3J-KL)") (class "Default")
      (node (ref "J3") (pin "18") (pinfunction "KL_18") (pintype "passive"))
      (node (ref "R14") (pin "2") (pinfunction "2_2") (pintype "passive"))
    )
    (net (code "40") (name "Net-(J3L-KL)") (class "Default")
      (node (ref "J3") (pin "2") (pinfunction "KL_2") (pintype "passive"))
      (node (ref "R6") (pin "2") (pinfunction "2_2") (pintype "passive"))
    )
    (net (code "41") (name "Net-(J3M-KL)") (class "Default")
      (node (ref "J3") (pin "20") (pinfunction "KL_20") (pintype "passive"))
      (node (ref "R15") (pin "2") (pinfunction "2_2") (pintype "passive"))
    )
    (net (code "42") (name "Net-(J3O-KL)") (class "Default")
      (node (ref "J3") (pin "22") (pinfunction "KL_22") (pintype "passive"))
      (node (ref "R16") (pin "2") (pinfunction "2_2") (pintype "passive"))
    )
    (net (code "43") (name "Net-(J3Q-KL)") (class "Default")
      (node (ref "J3") (pin "24") (pinfunction "KL_24") (pintype "passive"))
      (node (ref "R17") (pin "2") (pinfunction "2_2") (pintype "passive"))
    )
    (net (code "44") (name "Net-(J3S-KL)") (class "Default")
      (node (ref "J3") (pin "4") (pinfunction "KL_4") (pintype "passive"))
      (node (ref "R7") (pin "2") (pinfunction "2_2") (pintype "passive"))
    )
    (net (code "45") (name "Net-(J3U-KL)") (class "Default")
      (node (ref "J3") (pin "6") (pinfunction "KL_6") (pintype "passive"))
      (node (ref "R8") (pin "2") (pinfunction "2_2") (pintype "passive"))
    )
    (net (code "46") (name "Net-(J3W-KL)") (class "Default")
      (node (ref "J3") (pin "8") (pinfunction "KL_8") (pintype "passive"))
      (node (ref "R9") (pin "2") (pinfunction "2_2") (pintype "passive"))
    )
    (net (code "47") (name "Net-(JP1-Pad2)") (class "Default")
      (node (ref "JP1") (pin "2") (pinfunction "2_2") (pintype "passive"))
      (node (ref "RN1") (pin "1") (pinfunction "1_1") (pintype "passive"))
    )
    (net (code "48") (name "Net-(JP1-Pad4)") (class "Default")
      (node (ref "JP1") (pin "4") (pinfunction "4_4") (pintype "passive"))
      (node (ref "RN1") (pin "2") (pinfunction "2_2") (pintype "passive"))
    )
    (net (code "49") (name "Net-(JP1-Pad6)") (class "Default")
      (node (ref "JP1") (pin "6") (pinfunction "6_6") (pintype "passive"))
      (node (ref "RN1") (pin "3") (pinfunction "3_3") (pintype "passive"))
    )
    (net (code "50") (name "Net-(JP1-Pad8)") (class "Default")
      (node (ref "JP1") (pin "8") (pinfunction "8_8") (pintype "passive"))
      (node (ref "RN1") (pin "4") (pinfunction "4_4") (pintype "passive"))
    )
    (net (code "51") (name "Net-(LED1-PadC)") (class "Default")
      (node (ref "LED1") (pin "C") (pinfunction "C_C") (pintype "passive"))
      (node (ref "R4") (pin "2") (pinfunction "2_2") (pintype "passive"))
    )
    (net (code "52") (name "Net-(LED2-PadC)") (class "Default")
      (node (ref "LED2") (pin "C") (pinfunction "C_C") (pintype "passive"))
      (node (ref "R20") (pin "1") (pinfunction "1_1") (pintype "passive"))
    )
    (net (code "53") (name "Net-(LED3-PadC)") (class "Default")
      (node (ref "LED3") (pin "C") (pinfunction "C_C") (pintype "passive"))
      (node (ref "R21") (pin "1") (pinfunction "1_1") (pintype "passive"))
    )
    (net (code "54") (name "Net-(LED4-PadA)") (class "Default")
      (node (ref "LED4") (pin "A") (pinfunction "A_A") (pintype "passive"))
      (node (ref "R22") (pin "1") (pinfunction "1_1") (pintype "passive"))
    )
    (net (code "55") (name "Net-(LED5-PadC)") (class "Default")
      (node (ref "LED5") (pin "C") (pinfunction "C_C") (pintype "passive"))
      (node (ref "R30") (pin "2") (pinfunction "2_2") (pintype "passive"))
    )
    (net (code "56") (name "Net-(LED6-PadA)") (class "Default")
      (node (ref "LED6") (pin "A") (pinfunction "A_A") (pintype "passive"))
      (node (ref "R31") (pin "1") (pinfunction "1_1") (pintype "passive"))
    )
    (net (code "57") (name "Net-(LED7-PadA)") (class "Default")
      (node (ref "LED7") (pin "A") (pinfunction "A_A") (pintype "passive"))
      (node (ref "R32") (pin "1") (pinfunction "1_1") (pintype "passive"))
    )
    (net (code "58") (name "Net-(LED8-PadC)") (class "Default")
      (node (ref "LED8") (pin "C") (pinfunction "C_C") (pintype "passive"))
      (node (ref "R18") (pin "2") (pinfunction "2_2") (pintype "passive"))
    )
    (net (code "59") (name "Net-(LED9-PadC)") (class "Default")
      (node (ref "LED9") (pin "C") (pinfunction "C_C") (pintype "passive"))
      (node (ref "R19") (pin "2") (pinfunction "2_2") (pintype "passive"))
    )
    (net (code "60") (name "Net-(S1-O)") (class "Default")
      (node (ref "C1") (pin "1") (pinfunction "1_1") (pintype "passive"))
      (node (ref "S1") (pin "P$1") (pinfunction "O_P$1") (pintype "passive"))
      (node (ref "U1") (pin "P$2") (pinfunction "VIN_P$2") (pintype "bidirectional"))
      (node (ref "U1") (pin "P$3") (pinfunction "EN_P$3") (pintype "bidirectional"))
    )
    (net (code "61") (name "Net-(S1-P)") (class "Default")
      (node (ref "J1") (pin "1") (pinfunction "1_1") (pintype "passive"))
      (node (ref "S1") (pin "P$2") (pinfunction "P_P$2") (pintype "passive"))
    )
    (net (code "62") (name "Net-(U1-FB)") (class "Default")
      (node (ref "R2") (pin "1") (pinfunction "1_1") (pintype "passive"))
      (node (ref "R3") (pin "1") (pinfunction "1_1") (pintype "passive"))
      (node (ref "U1") (pin "P$5") (pinfunction "FB_P$5") (pintype "bidirectional"))
    )
    (net (code "63") (name "Net-(U1-PG)") (class "Default")
      (node (ref "R1") (pin "1") (pinfunction "1_1") (pintype "passive"))
      (node (ref "U1") (pin "P$8") (pinfunction "PG_P$8") (pintype "bidirectional"))
    )
    (net (code "64") (name "Net-(U1-SW)") (class "Default")
      (node (ref "L1") (pin "1") (pinfunction "1_1") (pintype "passive"))
      (node (ref "U1") (pin "P$7") (pinfunction "SW_P$7") (pintype "bidirectional"))
    )
    (net (code "65") (name "Net-(U3-1)") (class "Default")
      (node (ref "R5") (pin "2") (pinfunction "2_2") (pintype "passive"))
      (node (ref "U3") (pin "IREF") (pinfunction "1_IREF") (pintype "bidirectional"))
    )
    (net (code "66") (name "Net-(U3-11)") (class "Default")
      (node (ref "J2") (pin "2") (pinfunction "2_2") (pintype "passive"))
      (node (ref "U3") (pin "SCKO") (pinfunction "11_SCKO") (pintype "bidirectional"))
    )
    (net (code "67") (name "Net-(U3-12)") (class "Default")
      (node (ref "J2") (pin "1") (pinfunction "1_1") (pintype "passive"))
      (node (ref "U3") (pin "SDTO") (pinfunction "12_SDTO") (pintype "bidirectional"))
    )
    (net (code "68") (name "Net-(U6-PIO2)") (class "Default")
      (node (ref "R22") (pin "2") (pinfunction "2_2") (pintype "passive"))
      (node (ref "U6") (pin "P$19") (pinfunction "PIO2_P$19") (pintype "bidirectional"))
    )
    (net (code "69") (name "Net-(U6-PIO5)") (class "Default")
      (node (ref "R21") (pin "2") (pinfunction "2_2") (pintype "passive"))
      (node (ref "U6") (pin "P$21") (pinfunction "PIO5_P$21") (pintype "bidirectional"))
    )
    (net (code "70") (name "Net-(U6-PIO8)") (class "Default")
      (node (ref "R20") (pin "2") (pinfunction "2_2") (pintype "passive"))
      (node (ref "U6") (pin "P$31") (pinfunction "PIO8_P$31") (pintype "bidirectional"))
    )
    (net (code "71") (name "Net-(U11B-XI)") (class "Default")
      (node (ref "Q1") (pin "1") (pinfunction "1_1") (pintype "passive"))
      (node (ref "U11") (pin "28") (pinfunction "XI_28") (pintype "input"))
    )
    (net (code "72") (name "Net-(U11B-XO)") (class "Default")
      (node (ref "Q1") (pin "2") (pinfunction "2_2") (pintype "passive"))
      (node (ref "U11") (pin "29") (pinfunction "XO_29") (pintype "output"))
    )
    (net (code "73") (name "Net-(U13-~{DTR})") (class "Default")
      (node (ref "C13") (pin "2") (pinfunction "2_2") (pintype "passive"))
      (node (ref "U13") (pin "2") (pinfunction "~{DTR}_2") (pintype "output"))
    )
    (net (code "74") (name "SPI_CLK") (class "Default")
      (node (ref "TP_CLK") (pin "TP") (pinfunction "TP_TP") (pintype "input"))
      (node (ref "U11") (pin "4") (pinfunction "P7_4") (pintype "bidirectional"))
      (node (ref "U12") (pin "6") (pinfunction "SCK_6") (pintype "bidirectional"))
      (node (ref "U8") (pin "6") (pinfunction "SCK_6") (pintype "bidirectional"))
      (node (ref "U9") (pin "6") (pinfunction "SCK_6") (pintype "bidirectional"))
    )
    (net (code "75") (name "SPI_MISO") (class "Default")
      (node (ref "TP_MISO") (pin "TP") (pinfunction "TP_TP") (pintype "input"))
      (node (ref "U11") (pin "3") (pinfunction "P6_3") (pintype "bidirectional"))
      (node (ref "U12") (pin "2") (pinfunction "SO_2") (pintype "bidirectional"))
      (node (ref "U8") (pin "2") (pinfunction "SO_2") (pintype "bidirectional"))
      (node (ref "U9") (pin "2") (pinfunction "SO_2") (pintype "bidirectional"))
    )
    (net (code "76") (name "SPI_MOSI") (class "Default")
      (node (ref "TP_MOSI") (pin "TP") (pinfunction "TP_TP") (pintype "input"))
      (node (ref "U11") (pin "9") (pinfunction "P8_9") (pintype "bidirectional"))
      (node (ref "U12") (pin "5") (pinfunction "SI_5") (pintype "bidirectional"))
      (node (ref "U8") (pin "5") (pinfunction "SI_5") (pintype "bidirectional"))
      (node (ref "U9") (pin "5") (pinfunction "SI_5") (pintype "bidirectional"))
    )
    (net (code "77") (name "SPI_SS1") (class "Default")
      (node (ref "TP_SS1") (pin "TP") (pinfunction "TP_TP") (pintype "input"))
      (node (ref "U11") (pin "1") (pinfunction "P4_1") (pintype "bidirectional"))
      (node (ref "U8") (pin "1") (pinfunction "~{CS}_1") (pintype "bidirectional"))
    )
    (net (code "78") (name "SPI_SS2") (class "Default")
      (node (ref "TP_SS2") (pin "TP") (pinfunction "TP_TP") (pintype "input"))
      (node (ref "U11") (pin "2") (pinfunction "P5_2") (pintype "bidirectional"))
      (node (ref "U9") (pin "1") (pinfunction "~{CS}_1") (pintype "bidirectional"))
    )
    (net (code "79") (name "SPI_SS3") (class "Default")
      (node (ref "TP_SS3") (pin "TP") (pinfunction "TP_TP") (pintype "input"))
      (node (ref "U11") (pin "21") (pinfunction "P18_21") (pintype "bidirectional"))
      (node (ref "U12") (pin "1") (pinfunction "~{CS}_1") (pintype "bidirectional"))
    )
    (net (code "80") (name "TEST_LED0") (class "Default")
      (node (ref "LED8") (pin "A") (pinfunction "A_A") (pintype "passive"))
      (node (ref "U11") (pin "22") (pinfunction "P19_22") (pintype "bidirectional"))
    )
    (net (code "81") (name "TEST_LED1") (class "Default")
      (node (ref "LED9") (pin "A") (pinfunction "A_A") (pintype "passive"))
      (node (ref "U11") (pin "23") (pinfunction "P20_23") (pintype "bidirectional"))
    )
    (net (code "82") (name "TEST_SW") (class "Default")
      (node (ref "R26") (pin "1") (pinfunction "1_1") (pintype "passive"))
      (node (ref "SW2") (pin "P$2") (pinfunction "P$3_P$2") (pintype "bidirectional"))
      (node (ref "SW2") (pin "P$4") (pinfunction "P$4_P$4") (pintype "bidirectional"))
      (node (ref "U11") (pin "12") (pinfunction "P11_12") (pintype "bidirectional"))
    )
    (net (code "83") (name "USBDM") (class "Default")
      (node (ref "J4") (pin "2") (pinfunction "2_2") (pintype "passive"))
      (node (ref "U13") (pin "16") (pinfunction "USBDM_16") (pintype "bidirectional"))
    )
    (net (code "84") (name "USBDP") (class "Default")
      (node (ref "J4") (pin "3") (pinfunction "3_3") (pintype "passive"))
      (node (ref "U13") (pin "15") (pinfunction "USBDP_15") (pintype "bidirectional"))
    )
    (net (code "85") (name "USB_HPD") (class "Default")
      (node (ref "C14") (pin "1") (pinfunction "1_1") (pintype "passive"))
      (node (ref "U11") (pin "24") (pinfunction "P21_24") (pintype "bidirectional"))
      (node (ref "U13") (pin "17") (pinfunction "3V3OUT_17") (pintype "output"))
      (node (ref "U13") (pin "4") (pinfunction "VCCIO_4") (pintype "power_in"))
    )
    (net (code "86") (name "USB_RX") (class "Default")
      (node (ref "LED6") (pin "C") (pinfunction "C_C") (pintype "passive"))
      (node (ref "U13") (pin "22") (pinfunction "CBUS1_22") (pintype "bidirectional"))
    )
    (net (code "87") (name "USB_RXD") (class "Default")
      (node (ref "U11") (pin "37") (pinfunction "P30_37") (pintype "bidirectional"))
      (node (ref "U13") (pin "5") (pinfunction "RXD_5") (pintype "input"))
    )
    (net (code "88") (name "USB_TX") (class "Default")
      (node (ref "LED7") (pin "C") (pinfunction "C_C") (pintype "passive"))
      (node (ref "U13") (pin "23") (pinfunction "CBUS0_23") (pintype "bidirectional"))
    )
    (net (code "89") (name "USB_TXD") (class "Default")
      (node (ref "U11") (pin "38") (pinfunction "P31_38") (pintype "bidirectional"))
      (node (ref "U13") (pin "1") (pinfunction "TXD_1") (pintype "output"))
    )
    (net (code "90") (name "unconnected-(J4-Pad4)") (class "Default")
      (node (ref "J4") (pin "4") (pinfunction "4_4") (pintype "passive"))
    )
    (net (code "91") (name "unconnected-(JP2-Pad1)") (class "Default")
      (node (ref "JP2") (pin "1") (pinfunction "1_1") (pintype "passive"))
    )
    (net (code "92") (name "unconnected-(JP2-Pad8)") (class "Default")
      (node (ref "JP2") (pin "8") (pinfunction "8_8") (pintype "passive"))
    )
    (net (code "93") (name "unconnected-(JP2-Pad9)") (class "Default")
      (node (ref "JP2") (pin "9") (pinfunction "9_9") (pintype "passive"))
    )
    (net (code "94") (name "unconnected-(S1-S-PadP$3)") (class "Default")
      (node (ref "S1") (pin "P$3") (pinfunction "S_P$3") (pintype "passive"))
    )
    (net (code "95") (name "unconnected-(U6-AIO0-PadP$30)") (class "Default")
      (node (ref "U6") (pin "P$30") (pinfunction "AIO0_P$30") (pintype "bidirectional"))
    )
    (net (code "96") (name "unconnected-(U6-AIO1-PadP$35)") (class "Default")
      (node (ref "U6") (pin "P$35") (pinfunction "AIO1_P$35") (pintype "bidirectional"))
    )
    (net (code "97") (name "unconnected-(U6-PCM_CLK-PadP$7)") (class "Default")
      (node (ref "U6") (pin "P$7") (pinfunction "PCM_CLK_P$7") (pintype "bidirectional"))
    )
    (net (code "98") (name "unconnected-(U6-PCM_IN-PadP$9)") (class "Default")
      (node (ref "U6") (pin "P$9") (pinfunction "PCM_IN_P$9") (pintype "bidirectional"))
    )
    (net (code "99") (name "unconnected-(U6-PCM_OUT-PadP$10)") (class "Default")
      (node (ref "U6") (pin "P$10") (pinfunction "PCM_OUT_P$10") (pintype "bidirectional"))
    )
    (net (code "100") (name "unconnected-(U6-PCM_SYNC-PadP$8)") (class "Default")
      (node (ref "U6") (pin "P$8") (pinfunction "PCM_SYNC_P$8") (pintype "bidirectional"))
    )
    (net (code "101") (name "unconnected-(U6-PIO9-PadP$32)") (class "Default")
      (node (ref "U6") (pin "P$32") (pinfunction "PIO9_P$32") (pintype "bidirectional"))
    )
    (net (code "102") (name "unconnected-(U6-PIO10-PadP$33)") (class "Default")
      (node (ref "U6") (pin "P$33") (pinfunction "PIO10_P$33") (pintype "bidirectional"))
    )
    (net (code "103") (name "unconnected-(U6-PIO11-PadP$34)") (class "Default")
      (node (ref "U6") (pin "P$34") (pinfunction "PIO11_P$34") (pintype "bidirectional"))
    )
    (net (code "104") (name "unconnected-(U6-SPI_CLOCK-PadP$6)") (class "Default")
      (node (ref "U6") (pin "P$6") (pinfunction "SPI_CLOCK_P$6") (pintype "bidirectional"))
    )
    (net (code "105") (name "unconnected-(U6-SPI_CSB-PadP$23)") (class "Default")
      (node (ref "U6") (pin "P$23") (pinfunction "SPI_CSB_P$23") (pintype "bidirectional"))
    )
    (net (code "106") (name "unconnected-(U6-SPI_MISO-PadP$24)") (class "Default")
      (node (ref "U6") (pin "P$24") (pinfunction "SPI_MISO_P$24") (pintype "bidirectional"))
    )
    (net (code "107") (name "unconnected-(U6-SPI_MOSI-PadP$2)") (class "Default")
      (node (ref "U6") (pin "P$2") (pinfunction "SPI_MOSI_P$2") (pintype "bidirectional"))
    )
    (net (code "108") (name "unconnected-(U6-USB_D+-PadP$17)") (class "Default")
      (node (ref "U6") (pin "P$17") (pinfunction "USB_D+_P$17") (pintype "bidirectional"))
    )
    (net (code "109") (name "unconnected-(U6-USB_D--PadP$18)") (class "Default")
      (node (ref "U6") (pin "P$18") (pinfunction "USB_D-_P$18") (pintype "bidirectional"))
    )
    (net (code "110") (name "unconnected-(U8-NC-Pad3)") (class "Default")
      (node (ref "U8") (pin "3") (pinfunction "NC_3") (pintype "bidirectional"))
    )
    (net (code "111") (name "unconnected-(U9-NC-Pad3)") (class "Default")
      (node (ref "U9") (pin "3") (pinfunction "NC_3") (pintype "bidirectional"))
    )
    (net (code "112") (name "unconnected-(U11B-P22-Pad25)") (class "Default")
      (node (ref "U11") (pin "25") (pinfunction "P22_25") (pintype "bidirectional"))
    )
    (net (code "113") (name "unconnected-(U11B-P23-Pad26)") (class "Default")
      (node (ref "U11") (pin "26") (pinfunction "P23_26") (pintype "bidirectional"))
    )
    (net (code "114") (name "unconnected-(U11B-P24-Pad31)") (class "Default")
      (node (ref "U11") (pin "31") (pinfunction "P24_31") (pintype "bidirectional"))
    )
    (net (code "115") (name "unconnected-(U11B-P25-Pad32)") (class "Default")
      (node (ref "U11") (pin "32") (pinfunction "P25_32") (pintype "bidirectional"))
    )
    (net (code "116") (name "unconnected-(U11B-P26-Pad33)") (class "Default")
      (node (ref "U11") (pin "33") (pinfunction "P26_33") (pintype "bidirectional"))
    )
    (net (code "117") (name "unconnected-(U11B-P27-Pad34)") (class "Default")
      (node (ref "U11") (pin "34") (pinfunction "P27_34") (pintype "bidirectional"))
    )
    (net (code "118") (name "unconnected-(U13-CBUS2-Pad13)") (class "Default")
      (node (ref "U13") (pin "13") (pinfunction "CBUS2_13") (pintype "bidirectional"))
    )
    (net (code "119") (name "unconnected-(U13-CBUS3-Pad14)") (class "Default")
      (node (ref "U13") (pin "14") (pinfunction "CBUS3_14") (pintype "bidirectional"))
    )
    (net (code "120") (name "unconnected-(U13-CBUS4-Pad12)") (class "Default")
      (node (ref "U13") (pin "12") (pinfunction "CBUS4_12") (pintype "bidirectional"))
    )
    (net (code "121") (name "unconnected-(U13-OSCI-Pad27)") (class "Default")
      (node (ref "U13") (pin "27") (pinfunction "OSCI_27") (pintype "input"))
    )
    (net (code "122") (name "unconnected-(U13-OSCO-Pad28)") (class "Default")
      (node (ref "U13") (pin "28") (pinfunction "OSCO_28") (pintype "output"))
    )
    (net (code "123") (name "unconnected-(U13-~{CTS}-Pad11)") (class "Default")
      (node (ref "U13") (pin "11") (pinfunction "~{CTS}_11") (pintype "input"))
    )
    (net (code "124") (name "unconnected-(U13-~{DCD}-Pad10)") (class "Default")
      (node (ref "U13") (pin "10") (pinfunction "~{DCD}_10") (pintype "input"))
    )
    (net (code "125") (name "unconnected-(U13-~{DSR}-Pad9)") (class "Default")
      (node (ref "U13") (pin "9") (pinfunction "~{DSR}_9") (pintype "input"))
    )
    (net (code "126") (name "unconnected-(U13-~{RESET}-Pad19)") (class "Default")
      (node (ref "U13") (pin "19") (pinfunction "~{RESET}_19") (pintype "input"))
    )
    (net (code "127") (name "unconnected-(U13-~{RI}-Pad6)") (class "Default")
      (node (ref "U13") (pin "6") (pinfunction "~{RI}_6") (pintype "input"))
    )
    (net (code "128") (name "unconnected-(U13-~{RTS}-Pad3)") (class "Default")
      (node (ref "U13") (pin "3") (pinfunction "~{RTS}_3") (pintype "output"))
    )
    (net (code "129") (name "{slash}RESET") (class "Default")
      (node (ref "Q2") (pin "C") (pinfunction "C_C") (pintype "passive"))
      (node (ref "R27") (pin "1") (pinfunction "1_1") (pintype "passive"))
      (node (ref "SW3") (pin "P$2") (pinfunction "P$3_P$2") (pintype "bidirectional"))
      (node (ref "SW3") (pin "P$4") (pinfunction "P$4_P$4") (pintype "bidirectional"))
      (node (ref "U11") (pin "7") (pinfunction "RES/_7") (pintype "bidirectional"))
      (node (ref "U6") (pin "P$5") (pinfunction "RESET_P$5") (pintype "bidirectional"))
    )
  )
)
